# Schematic.net
KiCad netlist of a schematic drawn in EAGLE
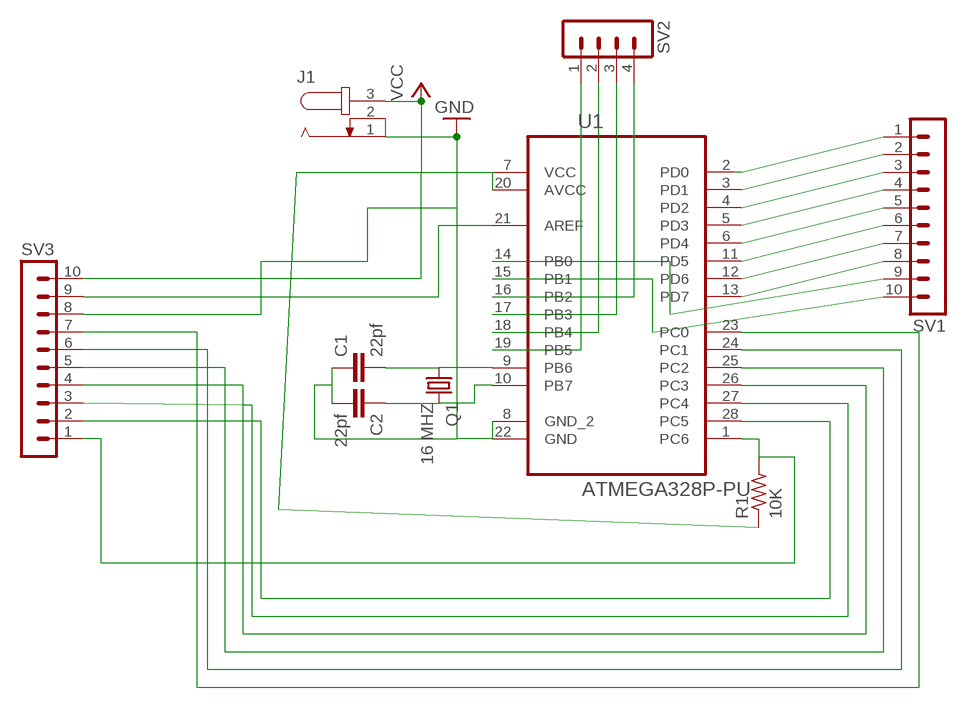
[diagram p0: schematic, sheet 1]

(export (version "E")
  (design (tool "Eeschema 10.0.6"))
  (components
    (comp (ref "C1")
      (value "22pf")
      (footprint "eagle-import:C025-024X044")
      (libsource (lib "eagle-import") (part "C-EU025-024X044"))
    )
    (comp (ref "C2")
      (value "22pf")
      (footprint "eagle-import:C025-024X044")
      (libsource (lib "eagle-import") (part "C-EU025-024X044"))
    )
    (comp (ref "J1")
      (value "JACK-PLUG0")
      (footprint "eagle-import:SPC4077")
      (libsource (lib "eagle-import") (part "JACK-PLUG0"))
    )
    (comp (ref "Q1")
      (value "16 MHZ")
      (footprint "eagle-import:HC49_S")
      (libsource (lib "eagle-import") (part "CRYSTALHC49S"))
    )
    (comp (ref "R1")
      (value "10K")
      (footprint "eagle-import:0207_10")
      (libsource (lib "eagle-import") (part "R-US_0207/10"))
    )
    (comp (ref "SV1")
      (value "MA10-1")
      (footprint "eagle-import:MA10-1")
      (libsource (lib "eagle-import") (part "MA10-1"))
    )
    (comp (ref "SV2")
      (value "MA04-1")
      (footprint "eagle-import:MA04-1")
      (libsource (lib "eagle-import") (part "MA04-1"))
    )
    (comp (ref "SV3")
      (value "MA10-1")
      (footprint "eagle-import:MA10-1")
      (libsource (lib "eagle-import") (part "MA10-1"))
    )
    (comp (ref "U1")
      (value "ATMEGA328P-PU")
      (footprint "eagle-import:DIP254P762X457-28")
      (libsource (lib "eagle-import") (part "ATMEGA328P-PU"))
    )
  )
  (nets
    (net (code "1") (name "GND") (class "Default")
      (node (ref "C1") (pin "1") (pinfunction "1_1") (pintype "passive"))
      (node (ref "C2") (pin "2") (pinfunction "2_2") (pintype "passive"))
      (node (ref "J1") (pin "1") (pinfunction "1_1") (pintype "passive"))
      (node (ref "J1") (pin "2") (pinfunction "2_2") (pintype "passive"))
      (node (ref "SV3") (pin "8") (pinfunction "8_8") (pintype "passive"))
      (node (ref "U1") (pin "22") (pinfunction "GND_22") (pintype "passive"))
      (node (ref "U1") (pin "8") (pinfunction "GND_2_8") (pintype "passive"))
    )
    (net (code "2") (name "Net-(U1-AREF)") (class "Default")
      (node (ref "SV3") (pin "9") (pinfunction "9_9") (pintype "passive"))
      (node (ref "U1") (pin "21") (pinfunction "AREF_21") (pintype "input"))
    )
    (net (code "3") (name "Net-(U1-PB0)") (class "Default")
      (node (ref "SV1") (pin "9") (pinfunction "9_9") (pintype "passive"))
      (node (ref "U1") (pin "14") (pinfunction "PB0_14") (pintype "bidirectional"))
    )
    (net (code "4") (name "Net-(U1-PB1)") (class "Default")
      (node (ref "SV1") (pin "10") (pinfunction "10_10") (pintype "passive"))
      (node (ref "U1") (pin "15") (pinfunction "PB1_15") (pintype "bidirectional"))
    )
    (net (code "5") (name "Net-(U1-PB2)") (class "Default")
      (node (ref "SV2") (pin "4") (pinfunction "4_4") (pintype "passive"))
      (node (ref "U1") (pin "16") (pinfunction "PB2_16") (pintype "bidirectional"))
    )
    (net (code "6") (name "Net-(U1-PB3)") (class "Default")
      (node (ref "SV2") (pin "3") (pinfunction "3_3") (pintype "passive"))
      (node (ref "U1") (pin "17") (pinfunction "PB3_17") (pintype "bidirectional"))
    )
    (net (code "7") (name "Net-(U1-PB4)") (class "Default")
      (node (ref "SV2") (pin "2") (pinfunction "2_2") (pintype "passive"))
      (node (ref "U1") (pin "18") (pinfunction "PB4_18") (pintype "bidirectional"))
    )
    (net (code "8") (name "Net-(U1-PB5)") (class "Default")
      (node (ref "SV2") (pin "1") (pinfunction "1_1") (pintype "passive"))
      (node (ref "U1") (pin "19") (pinfunction "PB5_19") (pintype "bidirectional"))
    )
    (net (code "9") (name "Net-(U1-PB6)") (class "Default")
      (node (ref "C1") (pin "2") (pinfunction "2_2") (pintype "passive"))
      (node (ref "Q1") (pin "1") (pinfunction "1_1") (pintype "passive"))
      (node (ref "U1") (pin "9") (pinfunction "PB6_9") (pintype "bidirectional"))
    )
    (net (code "10") (name "Net-(U1-PB7)") (class "Default")
      (node (ref "C2") (pin "1") (pinfunction "1_1") (pintype "passive"))
      (node (ref "Q1") (pin "2") (pinfunction "2_2") (pintype "passive"))
      (node (ref "U1") (pin "10") (pinfunction "PB7_10") (pintype "bidirectional"))
    )
    (net (code "11") (name "Net-(U1-PC0)") (class "Default")
      (node (ref "SV3") (pin "7") (pinfunction "7_7") (pintype "passive"))
      (node (ref "U1") (pin "23") (pinfunction "PC0_23") (pintype "bidirectional"))
    )
    (net (code "12") (name "Net-(U1-PC1)") (class "Default")
      (node (ref "SV3") (pin "6") (pinfunction "6_6") (pintype "passive"))
      (node (ref "U1") (pin "24") (pinfunction "PC1_24") (pintype "bidirectional"))
    )
    (net (code "13") (name "Net-(U1-PC2)") (class "Default")
      (node (ref "SV3") (pin "5") (pinfunction "5_5") (pintype "passive"))
      (node (ref "U1") (pin "25") (pinfunction "PC2_25") (pintype "bidirectional"))
    )
    (net (code "14") (name "Net-(U1-PC3)") (class "Default")
      (node (ref "SV3") (pin "4") (pinfunction "4_4") (pintype "passive"))
      (node (ref "U1") (pin "26") (pinfunction "PC3_26") (pintype "bidirectional"))
    )
    (net (code "15") (name "Net-(U1-PC4)") (class "Default")
      (node (ref "SV3") (pin "3") (pinfunction "3_3") (pintype "passive"))
      (node (ref "U1") (pin "27") (pinfunction "PC4_27") (pintype "bidirectional"))
    )
    (net (code "16") (name "Net-(U1-PC5)") (class "Default")
      (node (ref "SV3") (pin "2") (pinfunction "2_2") (pintype "passive"))
      (node (ref "U1") (pin "28") (pinfunction "PC5_28") (pintype "bidirectional"))
    )
    (net (code "17") (name "Net-(U1-PC6)") (class "Default")
      (node (ref "R1") (pin "2") (pinfunction "2_2") (pintype "passive"))
      (node (ref "SV3") (pin "1") (pinfunction "1_1") (pintype "passive"))
      (node (ref "U1") (pin "1") (pinfunction "PC6_1") (pintype "bidirectional"))
    )
    (net (code "18") (name "Net-(U1-PD0)") (class "Default")
      (node (ref "SV1") (pin "1") (pinfunction "1_1") (pintype "passive"))
      (node (ref "U1") (pin "2") (pinfunction "PD0_2") (pintype "bidirectional"))
    )
    (net (code "19") (name "Net-(U1-PD1)") (class "Default")
      (node (ref "SV1") (pin "2") (pinfunction "2_2") (pintype "passive"))
      (node (ref "U1") (pin "3") (pinfunction "PD1_3") (pintype "bidirectional"))
    )
    (net (code "20") (name "Net-(U1-PD2)") (class "Default")
      (node (ref "SV1") (pin "3") (pinfunction "3_3") (pintype "passive"))
      (node (ref "U1") (pin "4") (pinfunction "PD2_4") (pintype "bidirectional"))
    )
    (net (code "21") (name "Net-(U1-PD3)") (class "Default")
      (node (ref "SV1") (pin "4") (pinfunction "4_4") (pintype "passive"))
      (node (ref "U1") (pin "5") (pinfunction "PD3_5") (pintype "bidirectional"))
    )
    (net (code "22") (name "Net-(U1-PD4)") (class "Default")
      (node (ref "SV1") (pin "5") (pinfunction "5_5") (pintype "passive"))
      (node (ref "U1") (pin "6") (pinfunction "PD4_6") (pintype "bidirectional"))
    )
    (net (code "23") (name "Net-(U1-PD5)") (class "Default")
      (node (ref "SV1") (pin "6") (pinfunction "6_6") (pintype "passive"))
      (node (ref "U1") (pin "11") (pinfunction "PD5_11") (pintype "bidirectional"))
    )
    (net (code "24") (name "Net-(U1-PD6)") (class "Default")
      (node (ref "SV1") (pin "7") (pinfunction "7_7") (pintype "passive"))
      (node (ref "U1") (pin "12") (pinfunction "PD6_12") (pintype "bidirectional"))
    )
    (net (code "25") (name "Net-(U1-PD7)") (class "Default")
      (node (ref "SV1") (pin "8") (pinfunction "8_8") (pintype "passive"))
      (node (ref "U1") (pin "13") (pinfunction "PD7_13") (pintype "bidirectional"))
    )
    (net (code "26") (name "VCC") (class "Default")
      (node (ref "J1") (pin "3") (pinfunction "3_3") (pintype "passive"))
      (node (ref "R1") (pin "1") (pinfunction "1_1") (pintype "passive"))
      (node (ref "SV3") (pin "10") (pinfunction "10_10") (pintype "passive"))
      (node (ref "U1") (pin "20") (pinfunction "AVCC_20") (pintype "power_in"))
      (node (ref "U1") (pin "7") (pinfunction "VCC_7") (pintype "power_in"))
    )
  )
)
